# LED-PCB_DIG3.net
KiCad netlist of a schematic drawn in Altium Designer
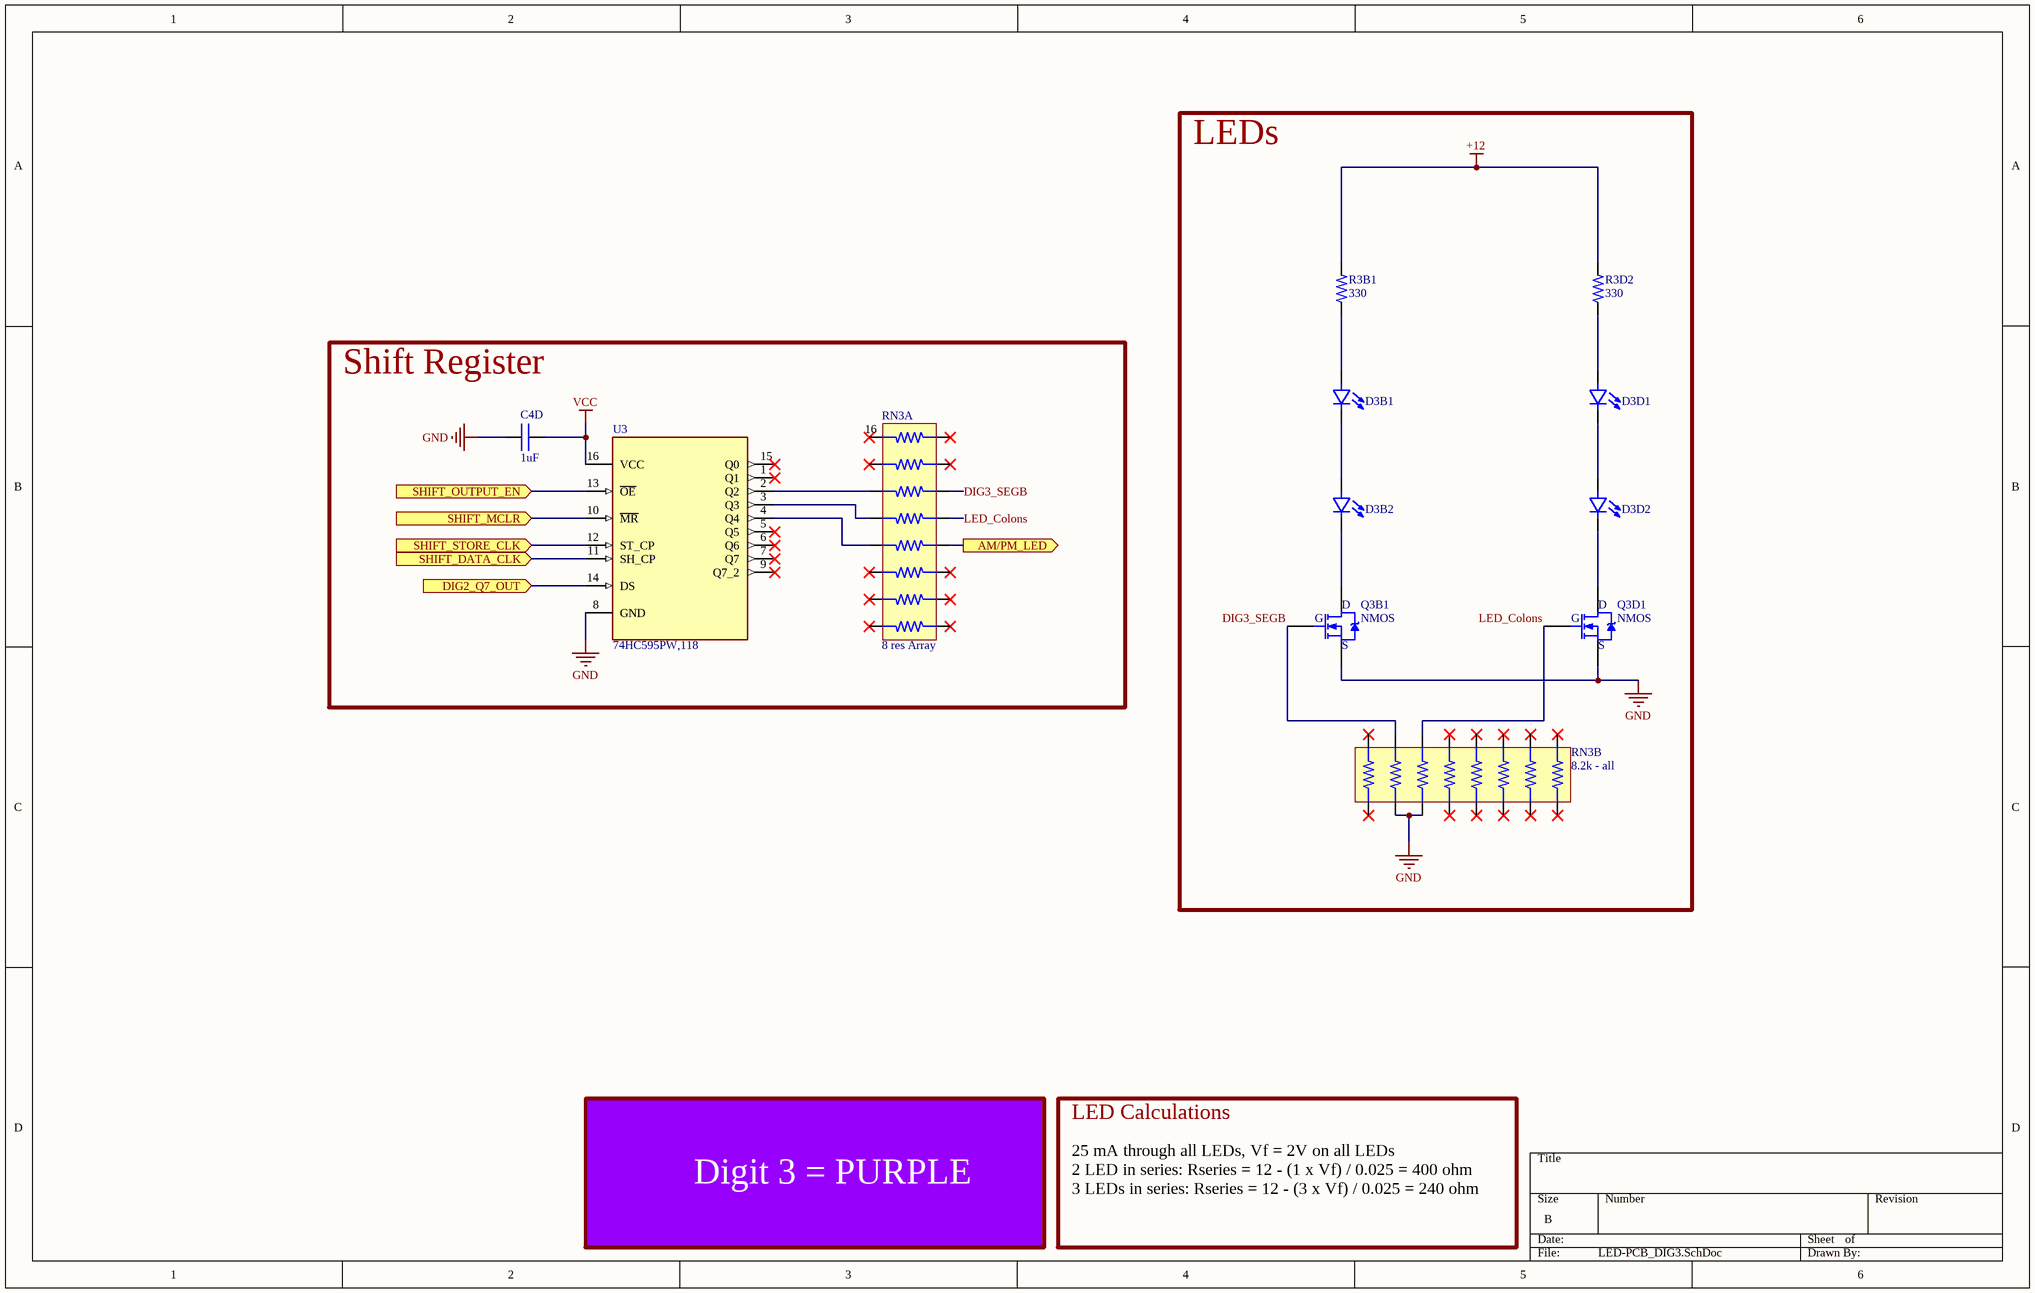
[diagram p0: LED-PCB_DIG3.SchDoc]

(export (version "E")
  (design (tool "Eeschema 10.0.6"))
  (components
    (comp (ref "C4D")
      (value "1uF")
      (footprint "sinking-clock:0402 CAP")
      (description "Capaicitor")
      (fields (field (name "MFR") "Samsung Microelectronics") (field (name "Comment") "CAP"))
      (libsource (lib "sinking-clock") (part "CAP"))
    )
    (comp (ref "D3B1")
      (value "LED - single")
      (footprint "sinking-clock:LED - 0603")
      (fields (field (name "MFR") "Wurth Elektronik"))
      (libsource (lib "sinking-clock") (part "LED - single"))
    )
    (comp (ref "D3B2")
      (value "LED - single")
      (footprint "sinking-clock:LED - 0603")
      (fields (field (name "MFR") "Wurth Elektronik"))
      (libsource (lib "sinking-clock") (part "LED - single"))
    )
    (comp (ref "D3D1")
      (value "LED - single")
      (footprint "sinking-clock:LED - 0603")
      (fields (field (name "MFR") "Wurth Elektronik"))
      (libsource (lib "sinking-clock") (part "LED - single"))
    )
    (comp (ref "D3D2")
      (value "LED - single")
      (footprint "sinking-clock:LED - 0603")
      (fields (field (name "MFR") "Wurth Elektronik"))
      (libsource (lib "sinking-clock") (part "LED - single"))
    )
    (comp (ref "Q3B1")
      (value "NMOS")
      (footprint "sinking-clock:SOT-23")
      (description "N-Channel MOSFET")
      (fields (field (name "MFR") "Diodes Incorporated"))
      (libsource (lib "sinking-clock") (part "NMOS"))
    )
    (comp (ref "Q3D1")
      (value "NMOS")
      (footprint "sinking-clock:SOT-23")
      (description "N-Channel MOSFET")
      (fields (field (name "MFR") "Diodes Incorporated"))
      (libsource (lib "sinking-clock") (part "NMOS"))
    )
    (comp (ref "R3B1")
      (value "330")
      (footprint "sinking-clock:0402 RES")
      (description "Resistor")
      (fields (field (name "MFR") "YAGEO") (field (name "Comment") "RES"))
      (libsource (lib "sinking-clock") (part "RES"))
    )
    (comp (ref "R3D2")
      (value "330")
      (footprint "sinking-clock:0402 RES")
      (description "Resistor")
      (fields (field (name "MFR") "YAGEO") (field (name "Comment") "RES"))
      (libsource (lib "sinking-clock") (part "RES"))
    )
    (comp (ref "RN3A")
      (value "8 res Array")
      (footprint "sinking-clock:EXB2HV331JV")
      (fields (field (name "MFR") "Panasonic Microelectronics"))
      (libsource (lib "sinking-clock") (part "8 res Array"))
    )
    (comp (ref "RN3B")
      (value "8.2k - all")
      (footprint "sinking-clock:MNR18ERAPJ822")
      (fields (field (name "MFR") "Rohm Semiconductor"))
      (libsource (lib "sinking-clock") (part "MNR18ERAPJ822"))
    )
    (comp (ref "U3")
      (value "74HC595PW,118")
      (footprint "sinking-clock:16-TSSOP")
      (description "Shift Shift Register 1 Element 8 Bit 16-TSSOP")
      (libsource (lib "sinking-clock") (part "74HC595PW,118"))
    )
  )
  (nets
    (net (code "1") (name "+12") (class "Default")
      (node (ref "R3B1") (pin "2") (pinfunction "2_2") (pintype "passive"))
      (node (ref "R3D2") (pin "2") (pinfunction "2_2") (pintype "passive"))
    )
    (net (code "2") (name "/AM{slash}PM_LED") (class "Default")
      (node (ref "RN3A") (pin "5") (pinfunction "5_5") (pintype "passive"))
    )
    (net (code "3") (name "/DIG2_Q7_OUT") (class "Default")
      (node (ref "U3") (pin "14") (pinfunction "DS_14") (pintype "input"))
    )
    (net (code "4") (name "/DIG3_SEGB") (class "Default")
      (node (ref "Q3B1") (pin "1") (pinfunction "G_1") (pintype "passive"))
      (node (ref "RN3A") (pin "3") (pinfunction "3_3") (pintype "passive"))
      (node (ref "RN3B") (pin "15") (pinfunction "15_15") (pintype "passive"))
    )
    (net (code "5") (name "/LED_Colons") (class "Default")
      (node (ref "Q3D1") (pin "1") (pinfunction "G_1") (pintype "passive"))
      (node (ref "RN3A") (pin "4") (pinfunction "4_4") (pintype "passive"))
      (node (ref "RN3B") (pin "14") (pinfunction "14_14") (pintype "passive"))
    )
    (net (code "6") (name "/SHIFT_DATA_CLK") (class "Default")
      (node (ref "U3") (pin "11") (pinfunction "SH_CP_11") (pintype "input"))
    )
    (net (code "7") (name "/SHIFT_MCLR") (class "Default")
      (node (ref "U3") (pin "10") (pinfunction "~{MR}_10") (pintype "input"))
    )
    (net (code "8") (name "/SHIFT_OUTPUT_EN") (class "Default")
      (node (ref "U3") (pin "13") (pinfunction "~{OE}_13") (pintype "input"))
    )
    (net (code "9") (name "/SHIFT_STORE_CLK") (class "Default")
      (node (ref "U3") (pin "12") (pinfunction "ST_CP_12") (pintype "input"))
    )
    (net (code "10") (name "GND") (class "Default")
      (node (ref "C4D") (pin "2") (pinfunction "2_2") (pintype "passive"))
      (node (ref "Q3B1") (pin "2") (pinfunction "S_2") (pintype "passive"))
      (node (ref "Q3D1") (pin "2") (pinfunction "S_2") (pintype "passive"))
      (node (ref "RN3B") (pin "2") (pinfunction "2_2") (pintype "passive"))
      (node (ref "RN3B") (pin "3") (pinfunction "3_3") (pintype "passive"))
      (node (ref "U3") (pin "8") (pinfunction "GND_8") (pintype "passive"))
    )
    (net (code "11") (name "Net-(D3B1-A)") (class "Default")
      (node (ref "D3B1") (pin "1") (pinfunction "A_1") (pintype "passive"))
      (node (ref "R3B1") (pin "1") (pinfunction "1_1") (pintype "passive"))
    )
    (net (code "12") (name "Net-(D3B1-C)") (class "Default")
      (node (ref "D3B1") (pin "2") (pinfunction "C_2") (pintype "passive"))
      (node (ref "D3B2") (pin "1") (pinfunction "A_1") (pintype "passive"))
    )
    (net (code "13") (name "Net-(D3B2-C)") (class "Default")
      (node (ref "D3B2") (pin "2") (pinfunction "C_2") (pintype "passive"))
      (node (ref "Q3B1") (pin "3") (pinfunction "D_3") (pintype "passive"))
    )
    (net (code "14") (name "Net-(D3D1-A)") (class "Default")
      (node (ref "D3D1") (pin "1") (pinfunction "A_1") (pintype "passive"))
      (node (ref "R3D2") (pin "1") (pinfunction "1_1") (pintype "passive"))
    )
    (net (code "15") (name "Net-(D3D1-C)") (class "Default")
      (node (ref "D3D1") (pin "2") (pinfunction "C_2") (pintype "passive"))
      (node (ref "D3D2") (pin "1") (pinfunction "A_1") (pintype "passive"))
    )
    (net (code "16") (name "Net-(D3D2-C)") (class "Default")
      (node (ref "D3D2") (pin "2") (pinfunction "C_2") (pintype "passive"))
      (node (ref "Q3D1") (pin "3") (pinfunction "D_3") (pintype "passive"))
    )
    (net (code "17") (name "Net-(U3-Q2)") (class "Default")
      (node (ref "RN3A") (pin "14") (pinfunction "14_14") (pintype "passive"))
      (node (ref "U3") (pin "2") (pinfunction "Q2_2") (pintype "output"))
    )
    (net (code "18") (name "Net-(U3-Q3)") (class "Default")
      (node (ref "RN3A") (pin "13") (pinfunction "13_13") (pintype "passive"))
      (node (ref "U3") (pin "3") (pinfunction "Q3_3") (pintype "output"))
    )
    (net (code "19") (name "Net-(U3-Q4)") (class "Default")
      (node (ref "RN3A") (pin "12") (pinfunction "12_12") (pintype "passive"))
      (node (ref "U3") (pin "4") (pinfunction "Q4_4") (pintype "output"))
    )
    (net (code "20") (name "VCC") (class "Default")
      (node (ref "C4D") (pin "1") (pinfunction "1_1") (pintype "passive"))
      (node (ref "U3") (pin "16") (pinfunction "VCC_16") (pintype "power_in"))
    )
    (net (code "21") (name "unconnected-(RN3A-Pad1)") (class "Default")
      (node (ref "RN3A") (pin "1") (pinfunction "1_1") (pintype "passive+no_connect"))
    )
    (net (code "22") (name "unconnected-(RN3A-Pad2)") (class "Default")
      (node (ref "RN3A") (pin "2") (pinfunction "2_2") (pintype "passive+no_connect"))
    )
    (net (code "23") (name "unconnected-(RN3A-Pad6)") (class "Default")
      (node (ref "RN3A") (pin "6") (pinfunction "6_6") (pintype "passive+no_connect"))
    )
    (net (code "24") (name "unconnected-(RN3A-Pad7)") (class "Default")
      (node (ref "RN3A") (pin "7") (pinfunction "7_7") (pintype "passive+no_connect"))
    )
    (net (code "25") (name "unconnected-(RN3A-Pad8)") (class "Default")
      (node (ref "RN3A") (pin "8") (pinfunction "8_8") (pintype "passive+no_connect"))
    )
    (net (code "26") (name "unconnected-(RN3A-Pad9)") (class "Default")
      (node (ref "RN3A") (pin "9") (pinfunction "9_9") (pintype "passive+no_connect"))
    )
    (net (code "27") (name "unconnected-(RN3A-Pad10)") (class "Default")
      (node (ref "RN3A") (pin "10") (pinfunction "10_10") (pintype "passive+no_connect"))
    )
    (net (code "28") (name "unconnected-(RN3A-Pad11)") (class "Default")
      (node (ref "RN3A") (pin "11") (pinfunction "11_11") (pintype "passive+no_connect"))
    )
    (net (code "29") (name "unconnected-(RN3A-Pad15)") (class "Default")
      (node (ref "RN3A") (pin "15") (pinfunction "15_15") (pintype "passive+no_connect"))
    )
    (net (code "30") (name "unconnected-(RN3A-Pad16)") (class "Default")
      (node (ref "RN3A") (pin "16") (pinfunction "16_16") (pintype "passive+no_connect"))
    )
    (net (code "31") (name "unconnected-(RN3B-Pad1)") (class "Default")
      (node (ref "RN3B") (pin "1") (pinfunction "1_1") (pintype "passive+no_connect"))
    )
    (net (code "32") (name "unconnected-(RN3B-Pad4)") (class "Default")
      (node (ref "RN3B") (pin "4") (pinfunction "4_4") (pintype "passive+no_connect"))
    )
    (net (code "33") (name "unconnected-(RN3B-Pad5)") (class "Default")
      (node (ref "RN3B") (pin "5") (pinfunction "5_5") (pintype "passive+no_connect"))
    )
    (net (code "34") (name "unconnected-(RN3B-Pad6)") (class "Default")
      (node (ref "RN3B") (pin "6") (pinfunction "6_6") (pintype "passive+no_connect"))
    )
    (net (code "35") (name "unconnected-(RN3B-Pad7)") (class "Default")
      (node (ref "RN3B") (pin "7") (pinfunction "7_7") (pintype "passive+no_connect"))
    )
    (net (code "36") (name "unconnected-(RN3B-Pad8)") (class "Default")
      (node (ref "RN3B") (pin "8") (pinfunction "8_8") (pintype "passive+no_connect"))
    )
    (net (code "37") (name "unconnected-(RN3B-Pad9)") (class "Default")
      (node (ref "RN3B") (pin "9") (pinfunction "9_9") (pintype "passive+no_connect"))
    )
    (net (code "38") (name "unconnected-(RN3B-Pad10)") (class "Default")
      (node (ref "RN3B") (pin "10") (pinfunction "10_10") (pintype "passive+no_connect"))
    )
    (net (code "39") (name "unconnected-(RN3B-Pad11)") (class "Default")
      (node (ref "RN3B") (pin "11") (pinfunction "11_11") (pintype "passive+no_connect"))
    )
    (net (code "40") (name "unconnected-(RN3B-Pad12)") (class "Default")
      (node (ref "RN3B") (pin "12") (pinfunction "12_12") (pintype "passive+no_connect"))
    )
    (net (code "41") (name "unconnected-(RN3B-Pad13)") (class "Default")
      (node (ref "RN3B") (pin "13") (pinfunction "13_13") (pintype "passive+no_connect"))
    )
    (net (code "42") (name "unconnected-(RN3B-Pad16)") (class "Default")
      (node (ref "RN3B") (pin "16") (pinfunction "16_16") (pintype "passive+no_connect"))
    )
    (net (code "43") (name "unconnected-(U3-Q0-Pad15)") (class "Default")
      (node (ref "U3") (pin "15") (pinfunction "Q0_15") (pintype "output+no_connect"))
    )
    (net (code "44") (name "unconnected-(U3-Q1-Pad1)") (class "Default")
      (node (ref "U3") (pin "1") (pinfunction "Q1_1") (pintype "output+no_connect"))
    )
    (net (code "45") (name "unconnected-(U3-Q5-Pad5)") (class "Default")
      (node (ref "U3") (pin "5") (pinfunction "Q5_5") (pintype "output+no_connect"))
    )
    (net (code "46") (name "unconnected-(U3-Q6-Pad6)") (class "Default")
      (node (ref "U3") (pin "6") (pinfunction "Q6_6") (pintype "output+no_connect"))
    )
    (net (code "47") (name "unconnected-(U3-Q7-Pad7)") (class "Default")
      (node (ref "U3") (pin "7") (pinfunction "Q7_7") (pintype "output+no_connect"))
    )
    (net (code "48") (name "unconnected-(U3-Q7_2-Pad9)") (class "Default")
      (node (ref "U3") (pin "9") (pinfunction "Q7_2_9") (pintype "output+no_connect"))
    )
  )
)
